# Wisp_v04.net
KiCad netlist of a schematic drawn in EAGLE
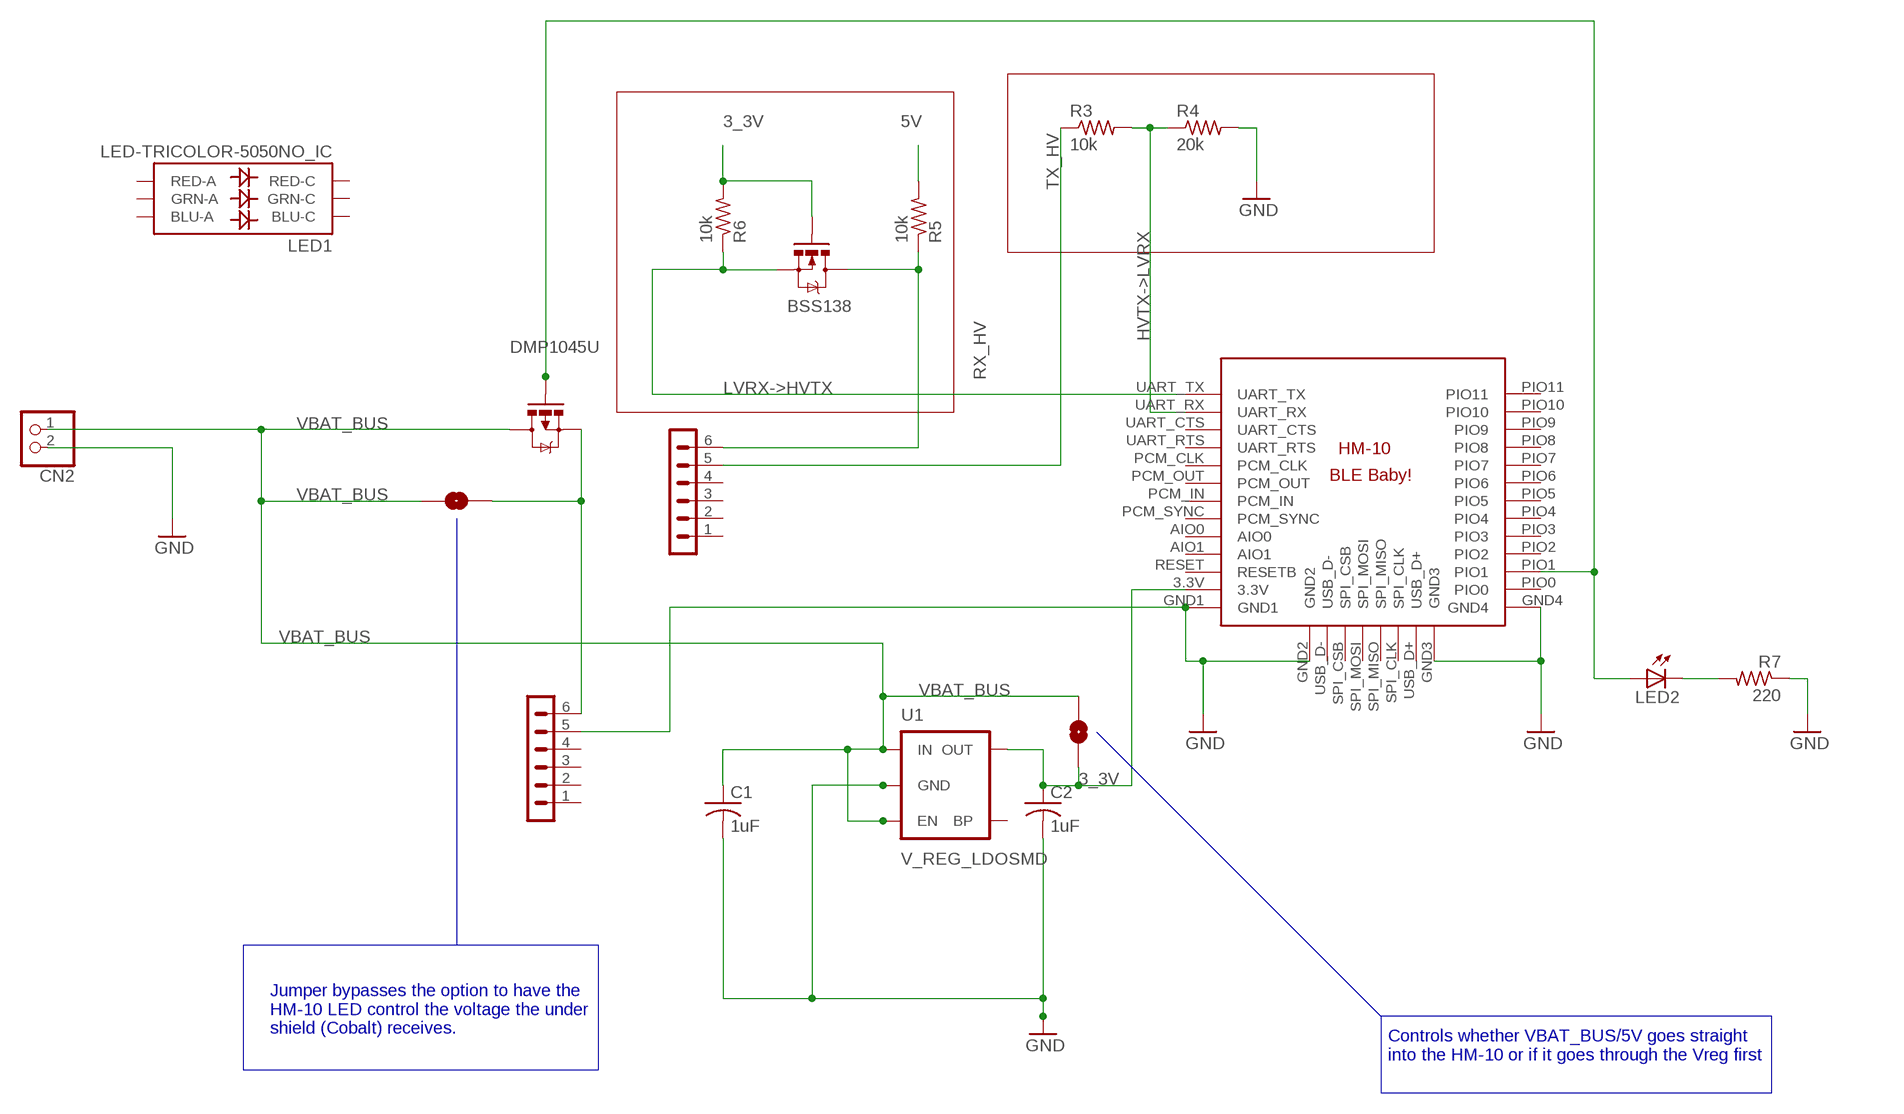
[diagram p0: schematic, sheet 1]

(export (version "E")
  (design (tool "Eeschema 10.0.6"))
  (components
    (comp (ref "BSS138")
      (value "MOSFET-NCHANNELSMD")
      (footprint "eagle-import:SOT23-3")
      (libsource (lib "eagle-import") (part "MOSFET-NCHANNELSMD"))
    )
    (comp (ref "C1")
      (value "1uF")
      (footprint "eagle-import:C0805K")
      (libsource (lib "eagle-import") (part "C-USC0805K"))
    )
    (comp (ref "C2")
      (value "1uF")
      (footprint "eagle-import:C0805K")
      (libsource (lib "eagle-import") (part "C-USC0805K"))
    )
    (comp (ref "CN2")
      (value "JST_2PIN-THM")
      (footprint "eagle-import:JST-PH-2-THM")
      (libsource (lib "eagle-import") (part "JST_2PIN-THM"))
    )
    (comp (ref "DMP1045U")
      (value "MOSFET-PCHANNELSMD")
      (footprint "eagle-import:SOT23-3")
      (libsource (lib "eagle-import") (part "MOSFET-PCHANNELSMD"))
    )
    (comp (ref "LED1")
      (value "LED-TRICOLOR-5050NO_IC")
      (footprint "eagle-import:LED-TRICOLOR-5050")
      (libsource (lib "eagle-import") (part "LED-TRICOLOR-5050NO_IC"))
    )
    (comp (ref "LED2")
      (value "LED0603")
      (footprint "eagle-import:LED-0603")
      (libsource (lib "eagle-import") (part "LED0603"))
    )
    (comp (ref "R3")
      (value "10k")
      (footprint "eagle-import:R0402")
      (libsource (lib "eagle-import") (part "R-US_R0402"))
    )
    (comp (ref "R4")
      (value "20k")
      (footprint "eagle-import:R0402")
      (libsource (lib "eagle-import") (part "R-US_R0402"))
    )
    (comp (ref "R5")
      (value "10k")
      (footprint "eagle-import:R0402")
      (libsource (lib "eagle-import") (part "R-US_R0402"))
    )
    (comp (ref "R6")
      (value "10k")
      (footprint "eagle-import:R0402")
      (libsource (lib "eagle-import") (part "R-US_R0402"))
    )
    (comp (ref "R7")
      (value "220")
      (footprint "eagle-import:R0402")
      (libsource (lib "eagle-import") (part "R-US_R0402"))
    )
    (comp (ref "SJ1")
      (value "SOLDERJUMPERNO")
      (footprint "eagle-import:SJ_2S-NO")
      (libsource (lib "eagle-import") (part "SOLDERJUMPERNO"))
    )
    (comp (ref "SJ2")
      (value "SOLDERJUMPERNO")
      (footprint "eagle-import:SJ_2S-NO")
      (libsource (lib "eagle-import") (part "SOLDERJUMPERNO"))
    )
    (comp (ref "U$1")
      (value "BLE-HM-10")
      (footprint "eagle-import:BLE-HM-10")
      (libsource (lib "eagle-import") (part "BLE-HM-10"))
    )
    (comp (ref "U$4")
      (value "1X6_SHORT_ROUND")
      (footprint "eagle-import:1X6_SHORT_ROUND")
      (libsource (lib "eagle-import") (part "1X6_SHORT_ROUND"))
    )
    (comp (ref "U$5")
      (value "1X6_SHORT_ROUND")
      (footprint "eagle-import:1X6_SHORT_ROUND")
      (libsource (lib "eagle-import") (part "1X6_SHORT_ROUND"))
    )
    (comp (ref "U1")
      (value "V_REG_LDOSMD")
      (footprint "eagle-import:SOT23-5")
      (libsource (lib "eagle-import") (part "V_REG_LDOSMD"))
    )
  )
  (nets
    (net (code "1") (name "/3_3V") (class "Default")
      (node (ref "BSS138") (pin "1") (pinfunction "G_1") (pintype "passive"))
      (node (ref "C2") (pin "1") (pinfunction "1_1") (pintype "passive"))
      (node (ref "R6") (pin "2") (pinfunction "2_2") (pintype "passive"))
      (node (ref "SJ1") (pin "1") (pinfunction "1_1") (pintype "passive"))
      (node (ref "U$1") (pin "3.3V") (pinfunction "3.3V_3.3V") (pintype "bidirectional"))
      (node (ref "U1") (pin "5") (pinfunction "OUT_5") (pintype "passive"))
    )
    (net (code "2") (name "/5V") (class "Default")
      (node (ref "R5") (pin "2") (pinfunction "2_2") (pintype "passive"))
    )
    (net (code "3") (name "/HVTX->LVRX") (class "Default")
      (node (ref "R3") (pin "2") (pinfunction "2_2") (pintype "passive"))
      (node (ref "R4") (pin "1") (pinfunction "1_1") (pintype "passive"))
      (node (ref "U$1") (pin "UART_RX") (pinfunction "UART_RX_UART_RX") (pintype "bidirectional"))
    )
    (net (code "4") (name "/LVRX->HVTX") (class "Default")
      (node (ref "BSS138") (pin "2") (pinfunction "S_2") (pintype "passive"))
      (node (ref "R6") (pin "1") (pinfunction "1_1") (pintype "passive"))
      (node (ref "U$1") (pin "UART_TX") (pinfunction "UART_TX_UART_TX") (pintype "bidirectional"))
    )
    (net (code "5") (name "/RX_HV") (class "Default")
      (node (ref "BSS138") (pin "3") (pinfunction "D_3") (pintype "passive"))
      (node (ref "R5") (pin "1") (pinfunction "1_1") (pintype "passive"))
      (node (ref "U$4") (pin "6") (pinfunction "6_6") (pintype "passive"))
    )
    (net (code "6") (name "/TX_HV") (class "Default")
      (node (ref "R3") (pin "1") (pinfunction "1_1") (pintype "passive"))
      (node (ref "U$4") (pin "5") (pinfunction "5_5") (pintype "passive"))
    )
    (net (code "7") (name "/VBAT_BUS") (class "Default")
      (node (ref "C1") (pin "1") (pinfunction "1_1") (pintype "passive"))
      (node (ref "CN2") (pin "1") (pinfunction "2_1") (pintype "passive"))
      (node (ref "DMP1045U") (pin "3") (pinfunction "D_3") (pintype "passive"))
      (node (ref "SJ1") (pin "2") (pinfunction "2_2") (pintype "passive"))
      (node (ref "SJ2") (pin "2") (pinfunction "2_2") (pintype "passive"))
      (node (ref "U1") (pin "1") (pinfunction "IN_1") (pintype "input"))
      (node (ref "U1") (pin "3") (pinfunction "EN_3") (pintype "input"))
    )
    (net (code "8") (name "GND") (class "Default")
      (node (ref "C1") (pin "2") (pinfunction "2_2") (pintype "passive"))
      (node (ref "C2") (pin "2") (pinfunction "2_2") (pintype "passive"))
      (node (ref "CN2") (pin "2") (pinfunction "1_2") (pintype "passive"))
      (node (ref "R4") (pin "2") (pinfunction "2_2") (pintype "passive"))
      (node (ref "R7") (pin "1") (pinfunction "1_1") (pintype "passive"))
      (node (ref "U$1") (pin "GND1") (pinfunction "GND1_GND1") (pintype "bidirectional"))
      (node (ref "U$1") (pin "GND2") (pinfunction "GND2_GND2") (pintype "bidirectional"))
      (node (ref "U$1") (pin "GND3") (pinfunction "GND3_GND3") (pintype "bidirectional"))
      (node (ref "U$1") (pin "GND4") (pinfunction "GND4_GND4") (pintype "bidirectional"))
      (node (ref "U$5") (pin "5") (pinfunction "5_5") (pintype "passive"))
      (node (ref "U1") (pin "2") (pinfunction "GND_2") (pintype "input"))
    )
    (net (code "9") (name "Net-(DMP1045U-G)") (class "Default")
      (node (ref "DMP1045U") (pin "1") (pinfunction "G_1") (pintype "passive"))
      (node (ref "LED2") (pin "A") (pinfunction "A_A") (pintype "passive"))
      (node (ref "U$1") (pin "PIO1") (pinfunction "PIO1_PIO1") (pintype "bidirectional"))
    )
    (net (code "10") (name "Net-(DMP1045U-S)") (class "Default")
      (node (ref "DMP1045U") (pin "2") (pinfunction "S_2") (pintype "passive"))
      (node (ref "SJ2") (pin "1") (pinfunction "1_1") (pintype "passive"))
      (node (ref "U$5") (pin "6") (pinfunction "6_6") (pintype "passive"))
    )
    (net (code "11") (name "Net-(LED2-PadC)") (class "Default")
      (node (ref "LED2") (pin "C") (pinfunction "C_C") (pintype "passive"))
      (node (ref "R7") (pin "2") (pinfunction "2_2") (pintype "passive"))
    )
    (net (code "12") (name "unconnected-(LED1-BLU-A-Pad3)") (class "Default")
      (node (ref "LED1") (pin "3") (pinfunction "BLU-A_3") (pintype "bidirectional"))
    )
    (net (code "13") (name "unconnected-(LED1-BLU-C-Pad4)") (class "Default")
      (node (ref "LED1") (pin "4") (pinfunction "BLU-C_4") (pintype "bidirectional"))
    )
    (net (code "14") (name "unconnected-(LED1-GRN-A-Pad1)") (class "Default")
      (node (ref "LED1") (pin "1") (pinfunction "GRN-A_1") (pintype "bidirectional"))
    )
    (net (code "15") (name "unconnected-(LED1-GRN-C-Pad6)") (class "Default")
      (node (ref "LED1") (pin "6") (pinfunction "GRN-C_6") (pintype "bidirectional"))
    )
    (net (code "16") (name "unconnected-(LED1-RED-A-Pad2)") (class "Default")
      (node (ref "LED1") (pin "2") (pinfunction "RED-A_2") (pintype "bidirectional"))
    )
    (net (code "17") (name "unconnected-(LED1-RED-C-Pad5)") (class "Default")
      (node (ref "LED1") (pin "5") (pinfunction "RED-C_5") (pintype "bidirectional"))
    )
    (net (code "18") (name "unconnected-(U$1-PadAIO0)") (class "Default")
      (node (ref "U$1") (pin "AIO0") (pinfunction "AIO0_AIO0") (pintype "bidirectional"))
    )
    (net (code "19") (name "unconnected-(U$1-PadAIO1)") (class "Default")
      (node (ref "U$1") (pin "AIO1") (pinfunction "AIO1_AIO1") (pintype "bidirectional"))
    )
    (net (code "20") (name "unconnected-(U$1-PadPCM_CLK)") (class "Default")
      (node (ref "U$1") (pin "PCM_CLK") (pinfunction "PCM_CLK_PCM_CLK") (pintype "bidirectional"))
    )
    (net (code "21") (name "unconnected-(U$1-PadPCM_IN)") (class "Default")
      (node (ref "U$1") (pin "PCM_IN") (pinfunction "PCM_IN_PCM_IN") (pintype "bidirectional"))
    )
    (net (code "22") (name "unconnected-(U$1-PadPCM_OUT)") (class "Default")
      (node (ref "U$1") (pin "PCM_OUT") (pinfunction "PCM_OUT_PCM_OUT") (pintype "bidirectional"))
    )
    (net (code "23") (name "unconnected-(U$1-PadPCM_SYNC)") (class "Default")
      (node (ref "U$1") (pin "PCM_SYNC") (pinfunction "PCM_SYNC_PCM_SYNC") (pintype "bidirectional"))
    )
    (net (code "24") (name "unconnected-(U$1-PadPIO0)") (class "Default")
      (node (ref "U$1") (pin "PIO0") (pinfunction "PIO0_PIO0") (pintype "bidirectional"))
    )
    (net (code "25") (name "unconnected-(U$1-PadPIO2)") (class "Default")
      (node (ref "U$1") (pin "PIO2") (pinfunction "PIO2_PIO2") (pintype "bidirectional"))
    )
    (net (code "26") (name "unconnected-(U$1-PadPIO3)") (class "Default")
      (node (ref "U$1") (pin "PIO3") (pinfunction "PIO3_PIO3") (pintype "bidirectional"))
    )
    (net (code "27") (name "unconnected-(U$1-PadPIO4)") (class "Default")
      (node (ref "U$1") (pin "PIO4") (pinfunction "PIO4_PIO4") (pintype "bidirectional"))
    )
    (net (code "28") (name "unconnected-(U$1-PadPIO5)") (class "Default")
      (node (ref "U$1") (pin "PIO5") (pinfunction "PIO5_PIO5") (pintype "bidirectional"))
    )
    (net (code "29") (name "unconnected-(U$1-PadPIO6)") (class "Default")
      (node (ref "U$1") (pin "PIO6") (pinfunction "PIO6_PIO6") (pintype "bidirectional"))
    )
    (net (code "30") (name "unconnected-(U$1-PadPIO7)") (class "Default")
      (node (ref "U$1") (pin "PIO7") (pinfunction "PIO7_PIO7") (pintype "bidirectional"))
    )
    (net (code "31") (name "unconnected-(U$1-PadPIO8)") (class "Default")
      (node (ref "U$1") (pin "PIO8") (pinfunction "PIO8_PIO8") (pintype "bidirectional"))
    )
    (net (code "32") (name "unconnected-(U$1-PadPIO9)") (class "Default")
      (node (ref "U$1") (pin "PIO9") (pinfunction "PIO9_PIO9") (pintype "bidirectional"))
    )
    (net (code "33") (name "unconnected-(U$1-PadPIO10)") (class "Default")
      (node (ref "U$1") (pin "PIO10") (pinfunction "PIO10_PIO10") (pintype "bidirectional"))
    )
    (net (code "34") (name "unconnected-(U$1-PadPIO11)") (class "Default")
      (node (ref "U$1") (pin "PIO11") (pinfunction "PIO11_PIO11") (pintype "bidirectional"))
    )
    (net (code "35") (name "unconnected-(U$1-PadSPI_CLK)") (class "Default")
      (node (ref "U$1") (pin "SPI_CLK") (pinfunction "SPI_CLK_SPI_CLK") (pintype "bidirectional"))
    )
    (net (code "36") (name "unconnected-(U$1-PadSPI_CSB)") (class "Default")
      (node (ref "U$1") (pin "SPI_CSB") (pinfunction "SPI_CSB_SPI_CSB") (pintype "bidirectional"))
    )
    (net (code "37") (name "unconnected-(U$1-PadSPI_MISO)") (class "Default")
      (node (ref "U$1") (pin "SPI_MISO") (pinfunction "SPI_MISO_SPI_MISO") (pintype "bidirectional"))
    )
    (net (code "38") (name "unconnected-(U$1-PadSPI_MOSI)") (class "Default")
      (node (ref "U$1") (pin "SPI_MOSI") (pinfunction "SPI_MOSI_SPI_MOSI") (pintype "bidirectional"))
    )
    (net (code "39") (name "unconnected-(U$1-PadUART_CTS)") (class "Default")
      (node (ref "U$1") (pin "UART_CTS") (pinfunction "UART_CTS_UART_CTS") (pintype "bidirectional"))
    )
    (net (code "40") (name "unconnected-(U$1-PadUART_RTS)") (class "Default")
      (node (ref "U$1") (pin "UART_RTS") (pinfunction "UART_RTS_UART_RTS") (pintype "bidirectional"))
    )
    (net (code "41") (name "unconnected-(U$1-PadUSB_D+)") (class "Default")
      (node (ref "U$1") (pin "USB_D+") (pinfunction "USB_D+_USB_D+") (pintype "bidirectional"))
    )
    (net (code "42") (name "unconnected-(U$1-PadUSB_D-)") (class "Default")
      (node (ref "U$1") (pin "USB_D-") (pinfunction "USB_D-_USB_D-") (pintype "bidirectional"))
    )
    (net (code "43") (name "unconnected-(U$1-RESETB-PadRESET)") (class "Default")
      (node (ref "U$1") (pin "RESET") (pinfunction "RESETB_RESET") (pintype "bidirectional"))
    )
    (net (code "44") (name "unconnected-(U$4-Pad1)") (class "Default")
      (node (ref "U$4") (pin "1") (pinfunction "1_1") (pintype "passive"))
    )
    (net (code "45") (name "unconnected-(U$4-Pad2)") (class "Default")
      (node (ref "U$4") (pin "2") (pinfunction "2_2") (pintype "passive"))
    )
    (net (code "46") (name "unconnected-(U$4-Pad3)") (class "Default")
      (node (ref "U$4") (pin "3") (pinfunction "3_3") (pintype "passive"))
    )
    (net (code "47") (name "unconnected-(U$4-Pad4)") (class "Default")
      (node (ref "U$4") (pin "4") (pinfunction "4_4") (pintype "passive"))
    )
    (net (code "48") (name "unconnected-(U$5-Pad1)") (class "Default")
      (node (ref "U$5") (pin "1") (pinfunction "1_1") (pintype "passive"))
    )
    (net (code "49") (name "unconnected-(U$5-Pad2)") (class "Default")
      (node (ref "U$5") (pin "2") (pinfunction "2_2") (pintype "passive"))
    )
    (net (code "50") (name "unconnected-(U$5-Pad3)") (class "Default")
      (node (ref "U$5") (pin "3") (pinfunction "3_3") (pintype "passive"))
    )
    (net (code "51") (name "unconnected-(U$5-Pad4)") (class "Default")
      (node (ref "U$5") (pin "4") (pinfunction "4_4") (pintype "passive"))
    )
    (net (code "52") (name "unconnected-(U1-BP-Pad4)") (class "Default")
      (node (ref "U1") (pin "4") (pinfunction "BP_4") (pintype "input"))
    )
  )
)
